# pic4.net
KiCad netlist of a schematic drawn in EAGLE
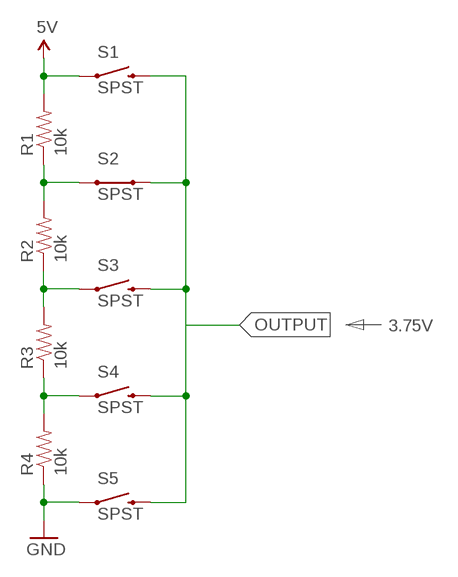
[diagram p0: schematic, sheet 1]

(export (version "E")
  (design (tool "Eeschema 10.0.6"))
  (components
    (comp (ref "R1")
      (value "10k")
      (footprint "eagle-import:0603-RES")
      (fields (field (name "PROD_ID") "RES-00818"))
      (libsource (lib "eagle-import") (part "330OHM1/10W1%(0603)"))
    )
    (comp (ref "R2")
      (value "10k")
      (footprint "eagle-import:0603-RES")
      (fields (field (name "PROD_ID") "RES-00818"))
      (libsource (lib "eagle-import") (part "330OHM1/10W1%(0603)"))
    )
    (comp (ref "R3")
      (value "10k")
      (footprint "eagle-import:0603-RES")
      (fields (field (name "PROD_ID") "RES-00818"))
      (libsource (lib "eagle-import") (part "330OHM1/10W1%(0603)"))
    )
    (comp (ref "R4")
      (value "10k")
      (footprint "eagle-import:0603-RES")
      (fields (field (name "PROD_ID") "RES-00818"))
      (libsource (lib "eagle-import") (part "330OHM1/10W1%(0603)"))
    )
    (comp (ref "S1")
      (value "SPST")
      (footprint "eagle-import:TACTILE-PTH-12MM")
      (libsource (lib "eagle-import") (part "SWITCH-MOMENTARY-212MM"))
    )
    (comp (ref "S2")
      (value "SPST")
      (footprint "eagle-import:TACTILE-PTH-12MM")
      (libsource (lib "eagle-import") (part "SWITCH-MOMENTARY-2-CLOSED"))
    )
    (comp (ref "S3")
      (value "SPST")
      (footprint "eagle-import:TACTILE-PTH-12MM")
      (libsource (lib "eagle-import") (part "SWITCH-MOMENTARY-212MM"))
    )
    (comp (ref "S4")
      (value "SPST")
      (footprint "eagle-import:TACTILE-PTH-12MM")
      (libsource (lib "eagle-import") (part "SWITCH-MOMENTARY-212MM"))
    )
    (comp (ref "S5")
      (value "SPST")
      (footprint "eagle-import:TACTILE-PTH-12MM")
      (libsource (lib "eagle-import") (part "SWITCH-MOMENTARY-212MM"))
    )
  )
  (nets
    (net (code "1") (name "5V") (class "Default")
      (node (ref "R1") (pin "2") (pinfunction "2_2") (pintype "passive"))
      (node (ref "S1") (pin "1") (pinfunction "1_1") (pintype "passive"))
    )
    (net (code "2") (name "GND") (class "Default")
      (node (ref "R4") (pin "1") (pinfunction "1_1") (pintype "passive"))
      (node (ref "S5") (pin "1") (pinfunction "1_1") (pintype "passive"))
    )
    (net (code "3") (name "Net-(R1-Pad1)") (class "Default")
      (node (ref "R1") (pin "1") (pinfunction "1_1") (pintype "passive"))
      (node (ref "R2") (pin "2") (pinfunction "2_2") (pintype "passive"))
      (node (ref "S2") (pin "1") (pinfunction "1_1") (pintype "passive"))
    )
    (net (code "4") (name "Net-(R2-Pad1)") (class "Default")
      (node (ref "R2") (pin "1") (pinfunction "1_1") (pintype "passive"))
      (node (ref "R3") (pin "2") (pinfunction "2_2") (pintype "passive"))
      (node (ref "S3") (pin "1") (pinfunction "1_1") (pintype "passive"))
    )
    (net (code "5") (name "Net-(R3-Pad1)") (class "Default")
      (node (ref "R3") (pin "1") (pinfunction "1_1") (pintype "passive"))
      (node (ref "R4") (pin "2") (pinfunction "2_2") (pintype "passive"))
      (node (ref "S4") (pin "1") (pinfunction "1_1") (pintype "passive"))
    )
    (net (code "6") (name "OUTPUT") (class "Default")
      (node (ref "S1") (pin "3") (pinfunction "2_3") (pintype "passive"))
      (node (ref "S2") (pin "3") (pinfunction "2_3") (pintype "passive"))
      (node (ref "S3") (pin "3") (pinfunction "2_3") (pintype "passive"))
      (node (ref "S4") (pin "3") (pinfunction "2_3") (pintype "passive"))
      (node (ref "S5") (pin "3") (pinfunction "2_3") (pintype "passive"))
    )
  )
)
